# LB_BIT_o21_number-v03_rev3_3.net
KiCad netlist of a schematic drawn in EAGLE
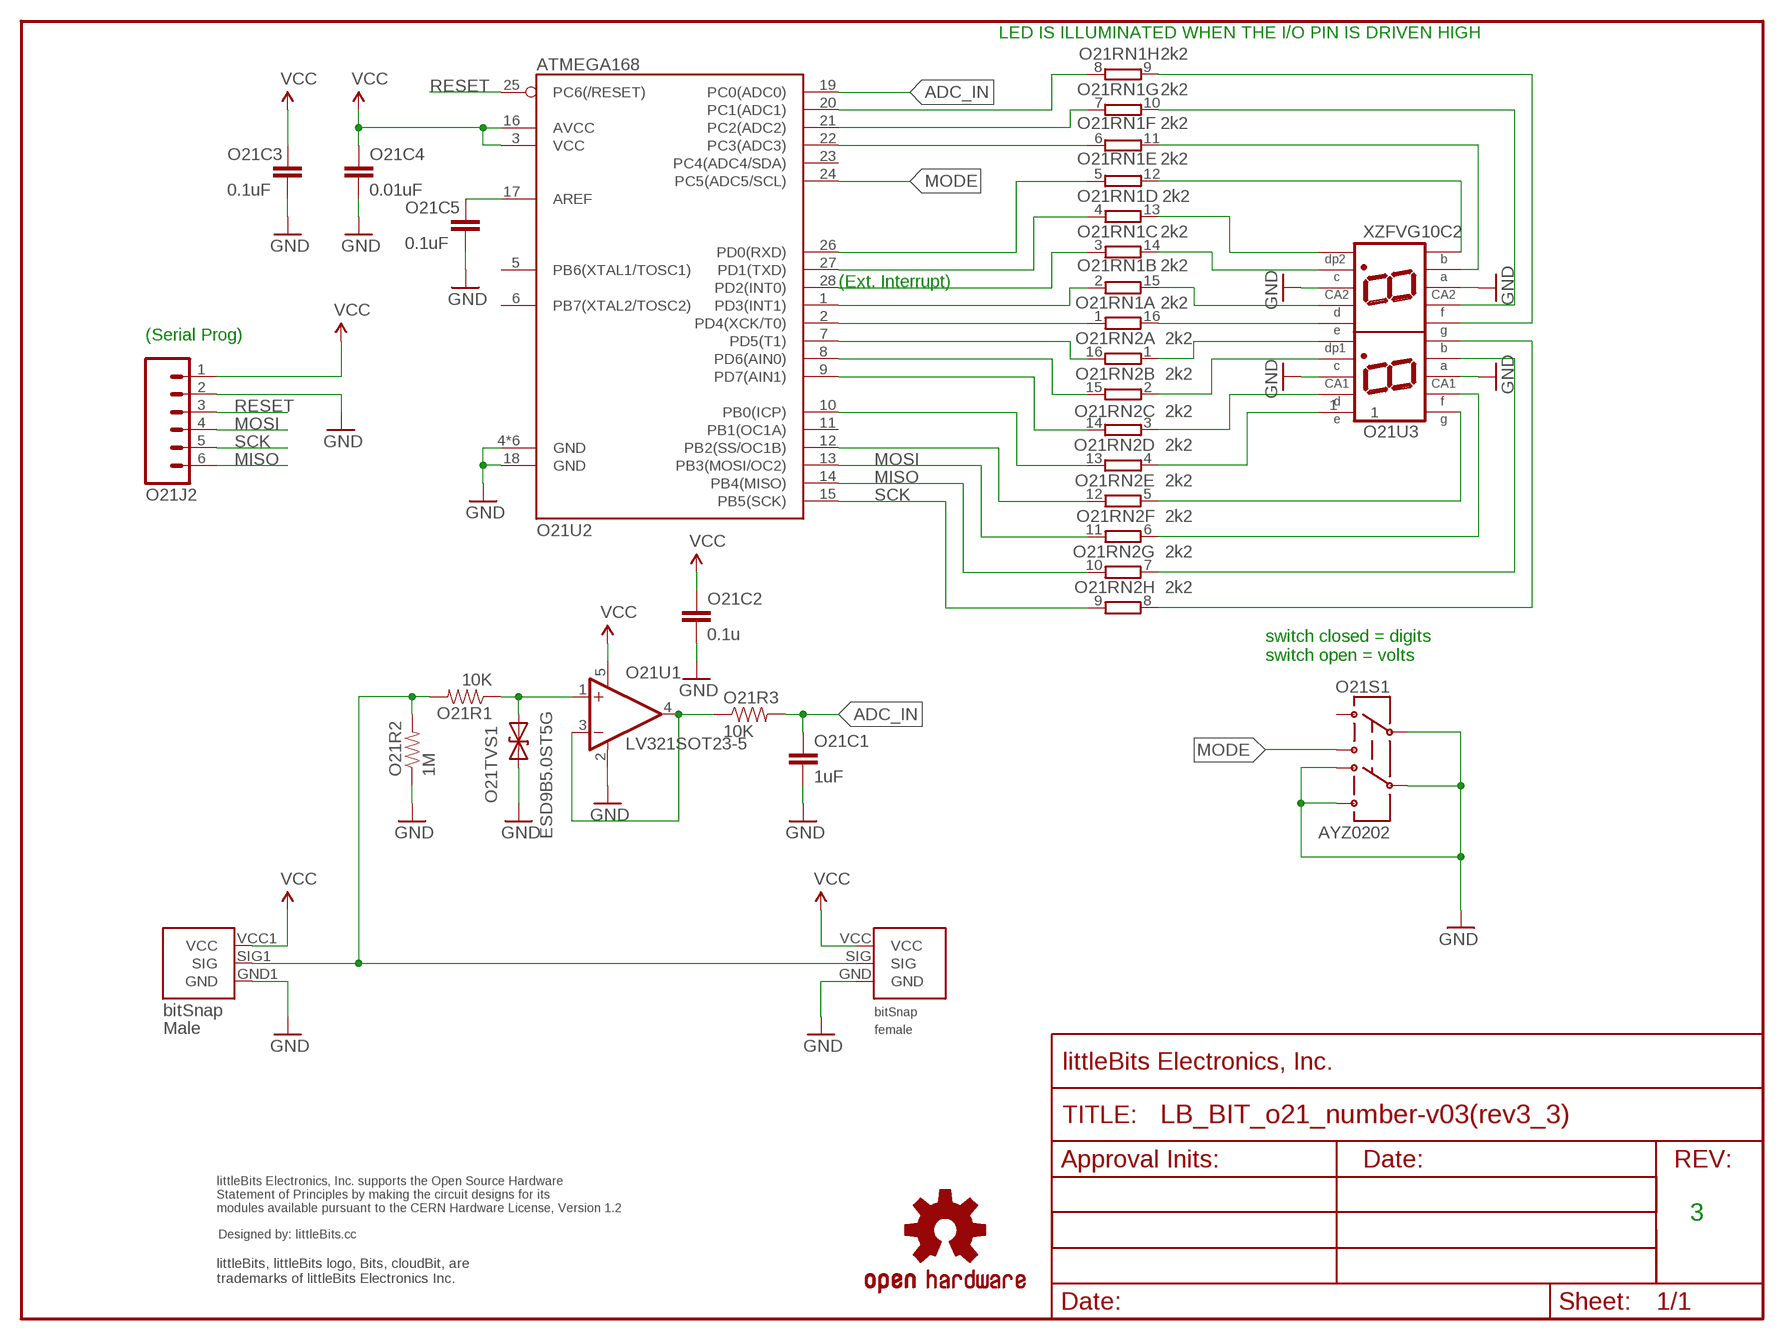
[diagram p0: schematic, sheet 1]

(export (version "E")
  (design (tool "Eeschema 10.0.6"))
  (components
    (comp (ref "O21BSF1")
      (value "BITSNAP_V03_FEMALE")
      (footprint "eagle-import:BITSNAP_V03_FEMALE")
      (libsource (lib "eagle-import") (part "BITSNAP_V03_FEMALE"))
    )
    (comp (ref "O21BSM1")
      (value "BITSNAP_V03_MALE")
      (footprint "eagle-import:BITSNAP_V03_MALE")
      (libsource (lib "eagle-import") (part "BITSNAP_V03_MALE"))
    )
    (comp (ref "O21C1")
      (value "1uF")
      (footprint "eagle-import:CAP-0603")
      (libsource (lib "eagle-import") (part "CAPCAP-0603"))
    )
    (comp (ref "O21C2")
      (value "0.1u")
      (footprint "eagle-import:CAP-0603")
      (libsource (lib "eagle-import") (part "CAPCAP-0603"))
    )
    (comp (ref "O21C3")
      (value "0.1uF")
      (footprint "eagle-import:CAP-0603")
      (libsource (lib "eagle-import") (part "CAPCAP-0603"))
    )
    (comp (ref "O21C4")
      (value "0.01uF")
      (footprint "eagle-import:CAP-0603")
      (libsource (lib "eagle-import") (part "CAPCAP-0603"))
    )
    (comp (ref "O21C5")
      (value "0.1uF")
      (footprint "eagle-import:CAP-0603")
      (libsource (lib "eagle-import") (part "CAPCAP-0603"))
    )
    (comp (ref "O21J2")
      (value "HRD-60.1INCH_NO_SILKSCREEN")
      (footprint "eagle-import:SIP6-SM-0.1IN-NOS.S.")
      (libsource (lib "eagle-import") (part "HRD-60.1INCH_NO_SILKSCREEN"))
    )
    (comp (ref "O21R1")
      (value "10K")
      (footprint "eagle-import:RES-0603")
      (libsource (lib "eagle-import") (part "RESISTOR0603"))
    )
    (comp (ref "O21R2")
      (value "1M")
      (footprint "eagle-import:RES-0603")
      (libsource (lib "eagle-import") (part "RESISTOR0603"))
    )
    (comp (ref "O21R3")
      (value "10K")
      (footprint "eagle-import:RES-0603")
      (libsource (lib "eagle-import") (part "RESISTOR0603"))
    )
    (comp (ref "O21RN1")
      (value "2k2")
      (footprint "eagle-import:EXB2HV")
      (libsource (lib "eagle-import") (part "RES_ARRAY8_DIPEXB2HV"))
    )
    (comp (ref "O21RN2")
      (value "2k2")
      (footprint "eagle-import:EXB2HV")
      (libsource (lib "eagle-import") (part "RES_ARRAY8_DIPEXB2HV"))
    )
    (comp (ref "O21S1")
      (value "AYZ0202")
      (footprint "eagle-import:AYZ0202")
      (libsource (lib "eagle-import") (part "AYZ0202"))
    )
    (comp (ref "O21TVS1")
      (value "ESD9B5.0ST5G")
      (footprint "eagle-import:SOD-923")
      (libsource (lib "eagle-import") (part "DIODE-TVSSOD-923"))
    )
    (comp (ref "O21U1")
      (value "LV321SOT23-5")
      (footprint "eagle-import:SOT23-5")
      (libsource (lib "eagle-import") (part "LV321SOT23-5"))
    )
    (comp (ref "O21U2")
      (value "ATMEGA168")
      (footprint "eagle-import:VQFN28")
      (libsource (lib "eagle-import") (part "ATMEGA168-28PINVFQFN-28"))
    )
    (comp (ref "O21U3")
      (value "XZFVG10C2")
      (footprint "eagle-import:LED-DUAL7SEG-SM")
      (libsource (lib "eagle-import") (part "LED-DUAL7SEG10.16MMDIGITS"))
    )
    (comp (ref "U$7")
      (value "OSHWCREDIT")
      (footprint "eagle-import:OSHWCREDIT")
      (libsource (lib "eagle-import") (part "OSHWCREDIT"))
    )
    (comp (ref "U$16")
      (value "FRAME-LETTER-OHWOHW")
      (footprint "eagle-import:FABDWG01-OHW")
      (libsource (lib "eagle-import") (part "FRAME-LETTER-OHWOHW"))
    )
    (comp (ref "U$27")
      (value "OSHW-LOGOL")
      (footprint "eagle-import:OSHW-LOGO-L")
      (libsource (lib "eagle-import") (part "OSHW-LOGOL"))
    )
  )
  (nets
    (net (code "1") (name "/MISO") (class "Default")
      (node (ref "O21J2") (pin "6") (pinfunction "6_6") (pintype "passive"))
      (node (ref "O21RN2") (pin "10") (pinfunction "2_10") (pintype "passive"))
      (node (ref "O21U2") (pin "14") (pinfunction "PB4(MISO)_14") (pintype "bidirectional"))
    )
    (net (code "2") (name "/MOSI") (class "Default")
      (node (ref "O21J2") (pin "4") (pinfunction "4_4") (pintype "passive"))
      (node (ref "O21RN2") (pin "11") (pinfunction "2_11") (pintype "passive"))
      (node (ref "O21U2") (pin "13") (pinfunction "PB3(MOSI/OC2)_13") (pintype "bidirectional"))
    )
    (net (code "3") (name "/RESET") (class "Default")
      (node (ref "O21J2") (pin "3") (pinfunction "3_3") (pintype "passive"))
      (node (ref "O21U2") (pin "25") (pinfunction "PC6(/RESET)_25") (pintype "bidirectional"))
    )
    (net (code "4") (name "/SCK") (class "Default")
      (node (ref "O21J2") (pin "5") (pinfunction "5_5") (pintype "passive"))
      (node (ref "O21RN2") (pin "9") (pinfunction "2_9") (pintype "passive"))
      (node (ref "O21U2") (pin "15") (pinfunction "PB5(SCK)_15") (pintype "bidirectional"))
    )
    (net (code "5") (name "ADC_IN") (class "Default")
      (node (ref "O21C1") (pin "1") (pinfunction "1_1") (pintype "passive"))
      (node (ref "O21R3") (pin "2") (pinfunction "2_2") (pintype "passive"))
      (node (ref "O21U2") (pin "19") (pinfunction "PC0(ADC0)_19") (pintype "bidirectional"))
    )
    (net (code "6") (name "GND") (class "Default")
      (node (ref "O21BSF1") (pin "GND") (pinfunction "GND_GND") (pintype "bidirectional"))
      (node (ref "O21BSM1") (pin "GND1") (pinfunction "GND_GND1") (pintype "bidirectional"))
      (node (ref "O21C1") (pin "2") (pinfunction "2_2") (pintype "passive"))
      (node (ref "O21C2") (pin "2") (pinfunction "2_2") (pintype "passive"))
      (node (ref "O21C3") (pin "2") (pinfunction "2_2") (pintype "passive"))
      (node (ref "O21C4") (pin "2") (pinfunction "2_2") (pintype "passive"))
      (node (ref "O21C5") (pin "2") (pinfunction "2_2") (pintype "passive"))
      (node (ref "O21J2") (pin "2") (pinfunction "2_2") (pintype "passive"))
      (node (ref "O21R2") (pin "1") (pinfunction "1_1") (pintype "passive"))
      (node (ref "O21S1") (pin "2") (pinfunction "2_2") (pintype "bidirectional"))
      (node (ref "O21S1") (pin "4") (pinfunction "4_4") (pintype "bidirectional"))
      (node (ref "O21S1") (pin "5") (pinfunction "5_5") (pintype "bidirectional"))
      (node (ref "O21S1") (pin "6") (pinfunction "6_6") (pintype "bidirectional"))
      (node (ref "O21TVS1") (pin "1") (pinfunction "A_1") (pintype "passive"))
      (node (ref "O21U1") (pin "2") (pinfunction "V-_2") (pintype "power_in"))
      (node (ref "O21U2") (pin "18") (pinfunction "GND_18") (pintype "bidirectional"))
      (node (ref "O21U2") (pin "4") (pinfunction "GND_4") (pintype "bidirectional"))
      (node (ref "O21U2") (pin "TH") (pinfunction "GND_TH") (pintype "bidirectional"))
      (node (ref "O21U2") (pin "TH@1") (pinfunction "GND_TH@1") (pintype "bidirectional"))
      (node (ref "O21U2") (pin "TH@2") (pinfunction "GND_TH@2") (pintype "bidirectional"))
      (node (ref "O21U2") (pin "TH@3") (pinfunction "GND_TH@3") (pintype "bidirectional"))
      (node (ref "O21U2") (pin "TH@4") (pinfunction "GND_TH@4") (pintype "bidirectional"))
      (node (ref "O21U3") (pin "13") (pinfunction "13_13") (pintype "passive"))
      (node (ref "O21U3") (pin "18") (pinfunction "18_18") (pintype "passive"))
      (node (ref "O21U3") (pin "3") (pinfunction "3_3") (pintype "passive"))
      (node (ref "O21U3") (pin "8") (pinfunction "8_8") (pintype "passive"))
    )
    (net (code "7") (name "MODE") (class "Default")
      (node (ref "O21S1") (pin "3") (pinfunction "3_3") (pintype "bidirectional"))
      (node (ref "O21U2") (pin "24") (pinfunction "PC5(ADC5/SCL)_24") (pintype "bidirectional"))
    )
    (net (code "8") (name "Net-(O21BSM1-SIG)") (class "Default")
      (node (ref "O21BSF1") (pin "SIG") (pinfunction "SIG_SIG") (pintype "bidirectional"))
      (node (ref "O21BSM1") (pin "SIG1") (pinfunction "SIG_SIG1") (pintype "bidirectional"))
      (node (ref "O21R1") (pin "2") (pinfunction "2_2") (pintype "passive"))
      (node (ref "O21R2") (pin "2") (pinfunction "2_2") (pintype "passive"))
    )
    (net (code "9") (name "Net-(O21RN1A-2)") (class "Default")
      (node (ref "O21RN1") (pin "16") (pinfunction "2_16") (pintype "passive"))
      (node (ref "O21U3") (pin "6") (pinfunction "6_6") (pintype "passive"))
    )
    (net (code "10") (name "Net-(O21RN1B-1)") (class "Default")
      (node (ref "O21RN1") (pin "2") (pinfunction "1_2") (pintype "passive"))
      (node (ref "O21U2") (pin "1") (pinfunction "PD3(INT1)_1") (pintype "bidirectional"))
    )
    (net (code "11") (name "Net-(O21RN1B-2)") (class "Default")
      (node (ref "O21RN1") (pin "15") (pinfunction "2_15") (pintype "passive"))
      (node (ref "O21U3") (pin "7") (pinfunction "7_7") (pintype "passive"))
    )
    (net (code "12") (name "Net-(O21RN1C-1)") (class "Default")
      (node (ref "O21RN1") (pin "3") (pinfunction "1_3") (pintype "passive"))
      (node (ref "O21U2") (pin "28") (pinfunction "PD2(INT0)_28") (pintype "bidirectional"))
    )
    (net (code "13") (name "Net-(O21RN1C-2)") (class "Default")
      (node (ref "O21RN1") (pin "14") (pinfunction "2_14") (pintype "passive"))
      (node (ref "O21U3") (pin "9") (pinfunction "9_9") (pintype "passive"))
    )
    (net (code "14") (name "Net-(O21RN1D-1)") (class "Default")
      (node (ref "O21RN1") (pin "4") (pinfunction "1_4") (pintype "passive"))
      (node (ref "O21U2") (pin "27") (pinfunction "PD1(TXD)_27") (pintype "bidirectional"))
    )
    (net (code "15") (name "Net-(O21RN1D-2)") (class "Default")
      (node (ref "O21RN1") (pin "13") (pinfunction "2_13") (pintype "passive"))
      (node (ref "O21U3") (pin "10") (pinfunction "10_10") (pintype "passive"))
    )
    (net (code "16") (name "Net-(O21RN1E-1)") (class "Default")
      (node (ref "O21RN1") (pin "5") (pinfunction "1_5") (pintype "passive"))
      (node (ref "O21U2") (pin "26") (pinfunction "PD0(RXD)_26") (pintype "bidirectional"))
    )
    (net (code "17") (name "Net-(O21RN1E-2)") (class "Default")
      (node (ref "O21RN1") (pin "12") (pinfunction "2_12") (pintype "passive"))
      (node (ref "O21U3") (pin "11") (pinfunction "11_11") (pintype "passive"))
    )
    (net (code "18") (name "Net-(O21RN1F-1)") (class "Default")
      (node (ref "O21RN1") (pin "6") (pinfunction "1_6") (pintype "passive"))
      (node (ref "O21U2") (pin "22") (pinfunction "PC3(ADC3)_22") (pintype "bidirectional"))
    )
    (net (code "19") (name "Net-(O21RN1F-2)") (class "Default")
      (node (ref "O21RN1") (pin "11") (pinfunction "2_11") (pintype "passive"))
      (node (ref "O21U3") (pin "12") (pinfunction "12_12") (pintype "passive"))
    )
    (net (code "20") (name "Net-(O21RN1G-1)") (class "Default")
      (node (ref "O21RN1") (pin "7") (pinfunction "1_7") (pintype "passive"))
      (node (ref "O21U2") (pin "21") (pinfunction "PC2(ADC2)_21") (pintype "bidirectional"))
    )
    (net (code "21") (name "Net-(O21RN1G-2)") (class "Default")
      (node (ref "O21RN1") (pin "10") (pinfunction "2_10") (pintype "passive"))
      (node (ref "O21U3") (pin "14") (pinfunction "14_14") (pintype "passive"))
    )
    (net (code "22") (name "Net-(O21RN1H-1)") (class "Default")
      (node (ref "O21RN1") (pin "8") (pinfunction "1_8") (pintype "passive"))
      (node (ref "O21U2") (pin "20") (pinfunction "PC1(ADC1)_20") (pintype "bidirectional"))
    )
    (net (code "23") (name "Net-(O21RN1H-2)") (class "Default")
      (node (ref "O21RN1") (pin "9") (pinfunction "2_9") (pintype "passive"))
      (node (ref "O21U3") (pin "15") (pinfunction "15_15") (pintype "passive"))
    )
    (net (code "24") (name "Net-(O21RN2-Pad1)") (class "Default")
      (node (ref "O21RN2") (pin "1") (pinfunction "1_1") (pintype "passive"))
      (node (ref "O21U3") (pin "5") (pinfunction "5_5") (pintype "passive"))
    )
    (net (code "25") (name "Net-(O21RN2A-2)") (class "Default")
      (node (ref "O21RN2") (pin "16") (pinfunction "2_16") (pintype "passive"))
      (node (ref "O21U2") (pin "7") (pinfunction "PD5(T1)_7") (pintype "bidirectional"))
    )
    (net (code "26") (name "Net-(O21RN2B-1)") (class "Default")
      (node (ref "O21RN2") (pin "2") (pinfunction "1_2") (pintype "passive"))
      (node (ref "O21U3") (pin "4") (pinfunction "4_4") (pintype "passive"))
    )
    (net (code "27") (name "Net-(O21RN2B-2)") (class "Default")
      (node (ref "O21RN2") (pin "15") (pinfunction "2_15") (pintype "passive"))
      (node (ref "O21U2") (pin "8") (pinfunction "PD6(AIN0)_8") (pintype "bidirectional"))
    )
    (net (code "28") (name "Net-(O21RN2C-1)") (class "Default")
      (node (ref "O21RN2") (pin "3") (pinfunction "1_3") (pintype "passive"))
      (node (ref "O21U3") (pin "2") (pinfunction "2_2") (pintype "passive"))
    )
    (net (code "29") (name "Net-(O21RN2C-2)") (class "Default")
      (node (ref "O21RN2") (pin "14") (pinfunction "2_14") (pintype "passive"))
      (node (ref "O21U2") (pin "9") (pinfunction "PD7(AIN1)_9") (pintype "bidirectional"))
    )
    (net (code "30") (name "Net-(O21RN2D-1)") (class "Default")
      (node (ref "O21RN2") (pin "4") (pinfunction "1_4") (pintype "passive"))
      (node (ref "O21U3") (pin "1") (pinfunction "1_1") (pintype "passive"))
    )
    (net (code "31") (name "Net-(O21RN2D-2)") (class "Default")
      (node (ref "O21RN2") (pin "13") (pinfunction "2_13") (pintype "passive"))
      (node (ref "O21U2") (pin "10") (pinfunction "PB0(ICP)_10") (pintype "bidirectional"))
    )
    (net (code "32") (name "Net-(O21RN2E-1)") (class "Default")
      (node (ref "O21RN2") (pin "5") (pinfunction "1_5") (pintype "passive"))
      (node (ref "O21U3") (pin "20") (pinfunction "20_20") (pintype "passive"))
    )
    (net (code "33") (name "Net-(O21RN2E-2)") (class "Default")
      (node (ref "O21RN2") (pin "12") (pinfunction "2_12") (pintype "passive"))
      (node (ref "O21U2") (pin "12") (pinfunction "PB2(SS/OC1B)_12") (pintype "bidirectional"))
    )
    (net (code "34") (name "Net-(O21RN2F-1)") (class "Default")
      (node (ref "O21RN2") (pin "6") (pinfunction "1_6") (pintype "passive"))
      (node (ref "O21U3") (pin "19") (pinfunction "19_19") (pintype "passive"))
    )
    (net (code "35") (name "Net-(O21RN2G-1)") (class "Default")
      (node (ref "O21RN2") (pin "7") (pinfunction "1_7") (pintype "passive"))
      (node (ref "O21U3") (pin "17") (pinfunction "17_17") (pintype "passive"))
    )
    (net (code "36") (name "Net-(O21RN2H-1)") (class "Default")
      (node (ref "O21RN2") (pin "8") (pinfunction "1_8") (pintype "passive"))
      (node (ref "O21U3") (pin "16") (pinfunction "16_16") (pintype "passive"))
    )
    (net (code "37") (name "Net-(O21TVS1-C)") (class "Default")
      (node (ref "O21R1") (pin "1") (pinfunction "1_1") (pintype "passive"))
      (node (ref "O21TVS1") (pin "2") (pinfunction "C_2") (pintype "passive"))
      (node (ref "O21U1") (pin "1") (pinfunction "+IN_1") (pintype "input"))
    )
    (net (code "38") (name "Net-(O21U1--IN)") (class "Default")
      (node (ref "O21R3") (pin "1") (pinfunction "1_1") (pintype "passive"))
      (node (ref "O21U1") (pin "3") (pinfunction "-IN_3") (pintype "input"))
      (node (ref "O21U1") (pin "4") (pinfunction "OUT_4") (pintype "output"))
    )
    (net (code "39") (name "Net-(O21U2-AREF)") (class "Default")
      (node (ref "O21C5") (pin "1") (pinfunction "1_1") (pintype "passive"))
      (node (ref "O21U2") (pin "17") (pinfunction "AREF_17") (pintype "bidirectional"))
    )
    (net (code "40") (name "Net-(O21U2-PD4(XCK{slash}T0))") (class "Default")
      (node (ref "O21RN1") (pin "1") (pinfunction "1_1") (pintype "passive"))
      (node (ref "O21U2") (pin "2") (pinfunction "PD4(XCK/T0)_2") (pintype "bidirectional"))
    )
    (net (code "41") (name "VCC") (class "Default")
      (node (ref "O21BSF1") (pin "VCC") (pinfunction "VCC_VCC") (pintype "bidirectional"))
      (node (ref "O21BSM1") (pin "VCC1") (pinfunction "VCC_VCC1") (pintype "bidirectional"))
      (node (ref "O21C2") (pin "1") (pinfunction "1_1") (pintype "passive"))
      (node (ref "O21C3") (pin "1") (pinfunction "1_1") (pintype "passive"))
      (node (ref "O21C4") (pin "1") (pinfunction "1_1") (pintype "passive"))
      (node (ref "O21J2") (pin "1") (pinfunction "1_1") (pintype "passive"))
      (node (ref "O21U1") (pin "5") (pinfunction "V+_5") (pintype "power_in"))
      (node (ref "O21U2") (pin "16") (pinfunction "AVCC_16") (pintype "bidirectional"))
      (node (ref "O21U2") (pin "3") (pinfunction "VCC_3") (pintype "bidirectional"))
    )
    (net (code "42") (name "unconnected-(O21S1-Pad1)") (class "Default")
      (node (ref "O21S1") (pin "1") (pinfunction "1_1") (pintype "bidirectional"))
    )
    (net (code "43") (name "unconnected-(O21U2-PB1(OC1A)-Pad11)") (class "Default")
      (node (ref "O21U2") (pin "11") (pinfunction "PB1(OC1A)_11") (pintype "bidirectional"))
    )
    (net (code "44") (name "unconnected-(O21U2-PB6(XTAL1{slash}TOSC1)-Pad5)") (class "Default")
      (node (ref "O21U2") (pin "5") (pinfunction "PB6(XTAL1/TOSC1)_5") (pintype "bidirectional"))
    )
    (net (code "45") (name "unconnected-(O21U2-PB7(XTAL2{slash}TOSC2)-Pad6)") (class "Default")
      (node (ref "O21U2") (pin "6") (pinfunction "PB7(XTAL2/TOSC2)_6") (pintype "bidirectional"))
    )
    (net (code "46") (name "unconnected-(O21U2-PC4(ADC4{slash}SDA)-Pad23)") (class "Default")
      (node (ref "O21U2") (pin "23") (pinfunction "PC4(ADC4/SDA)_23") (pintype "bidirectional"))
    )
  )
)
